# Fastino-connectors.net
KiCad netlist of a schematic drawn in Altium Designer
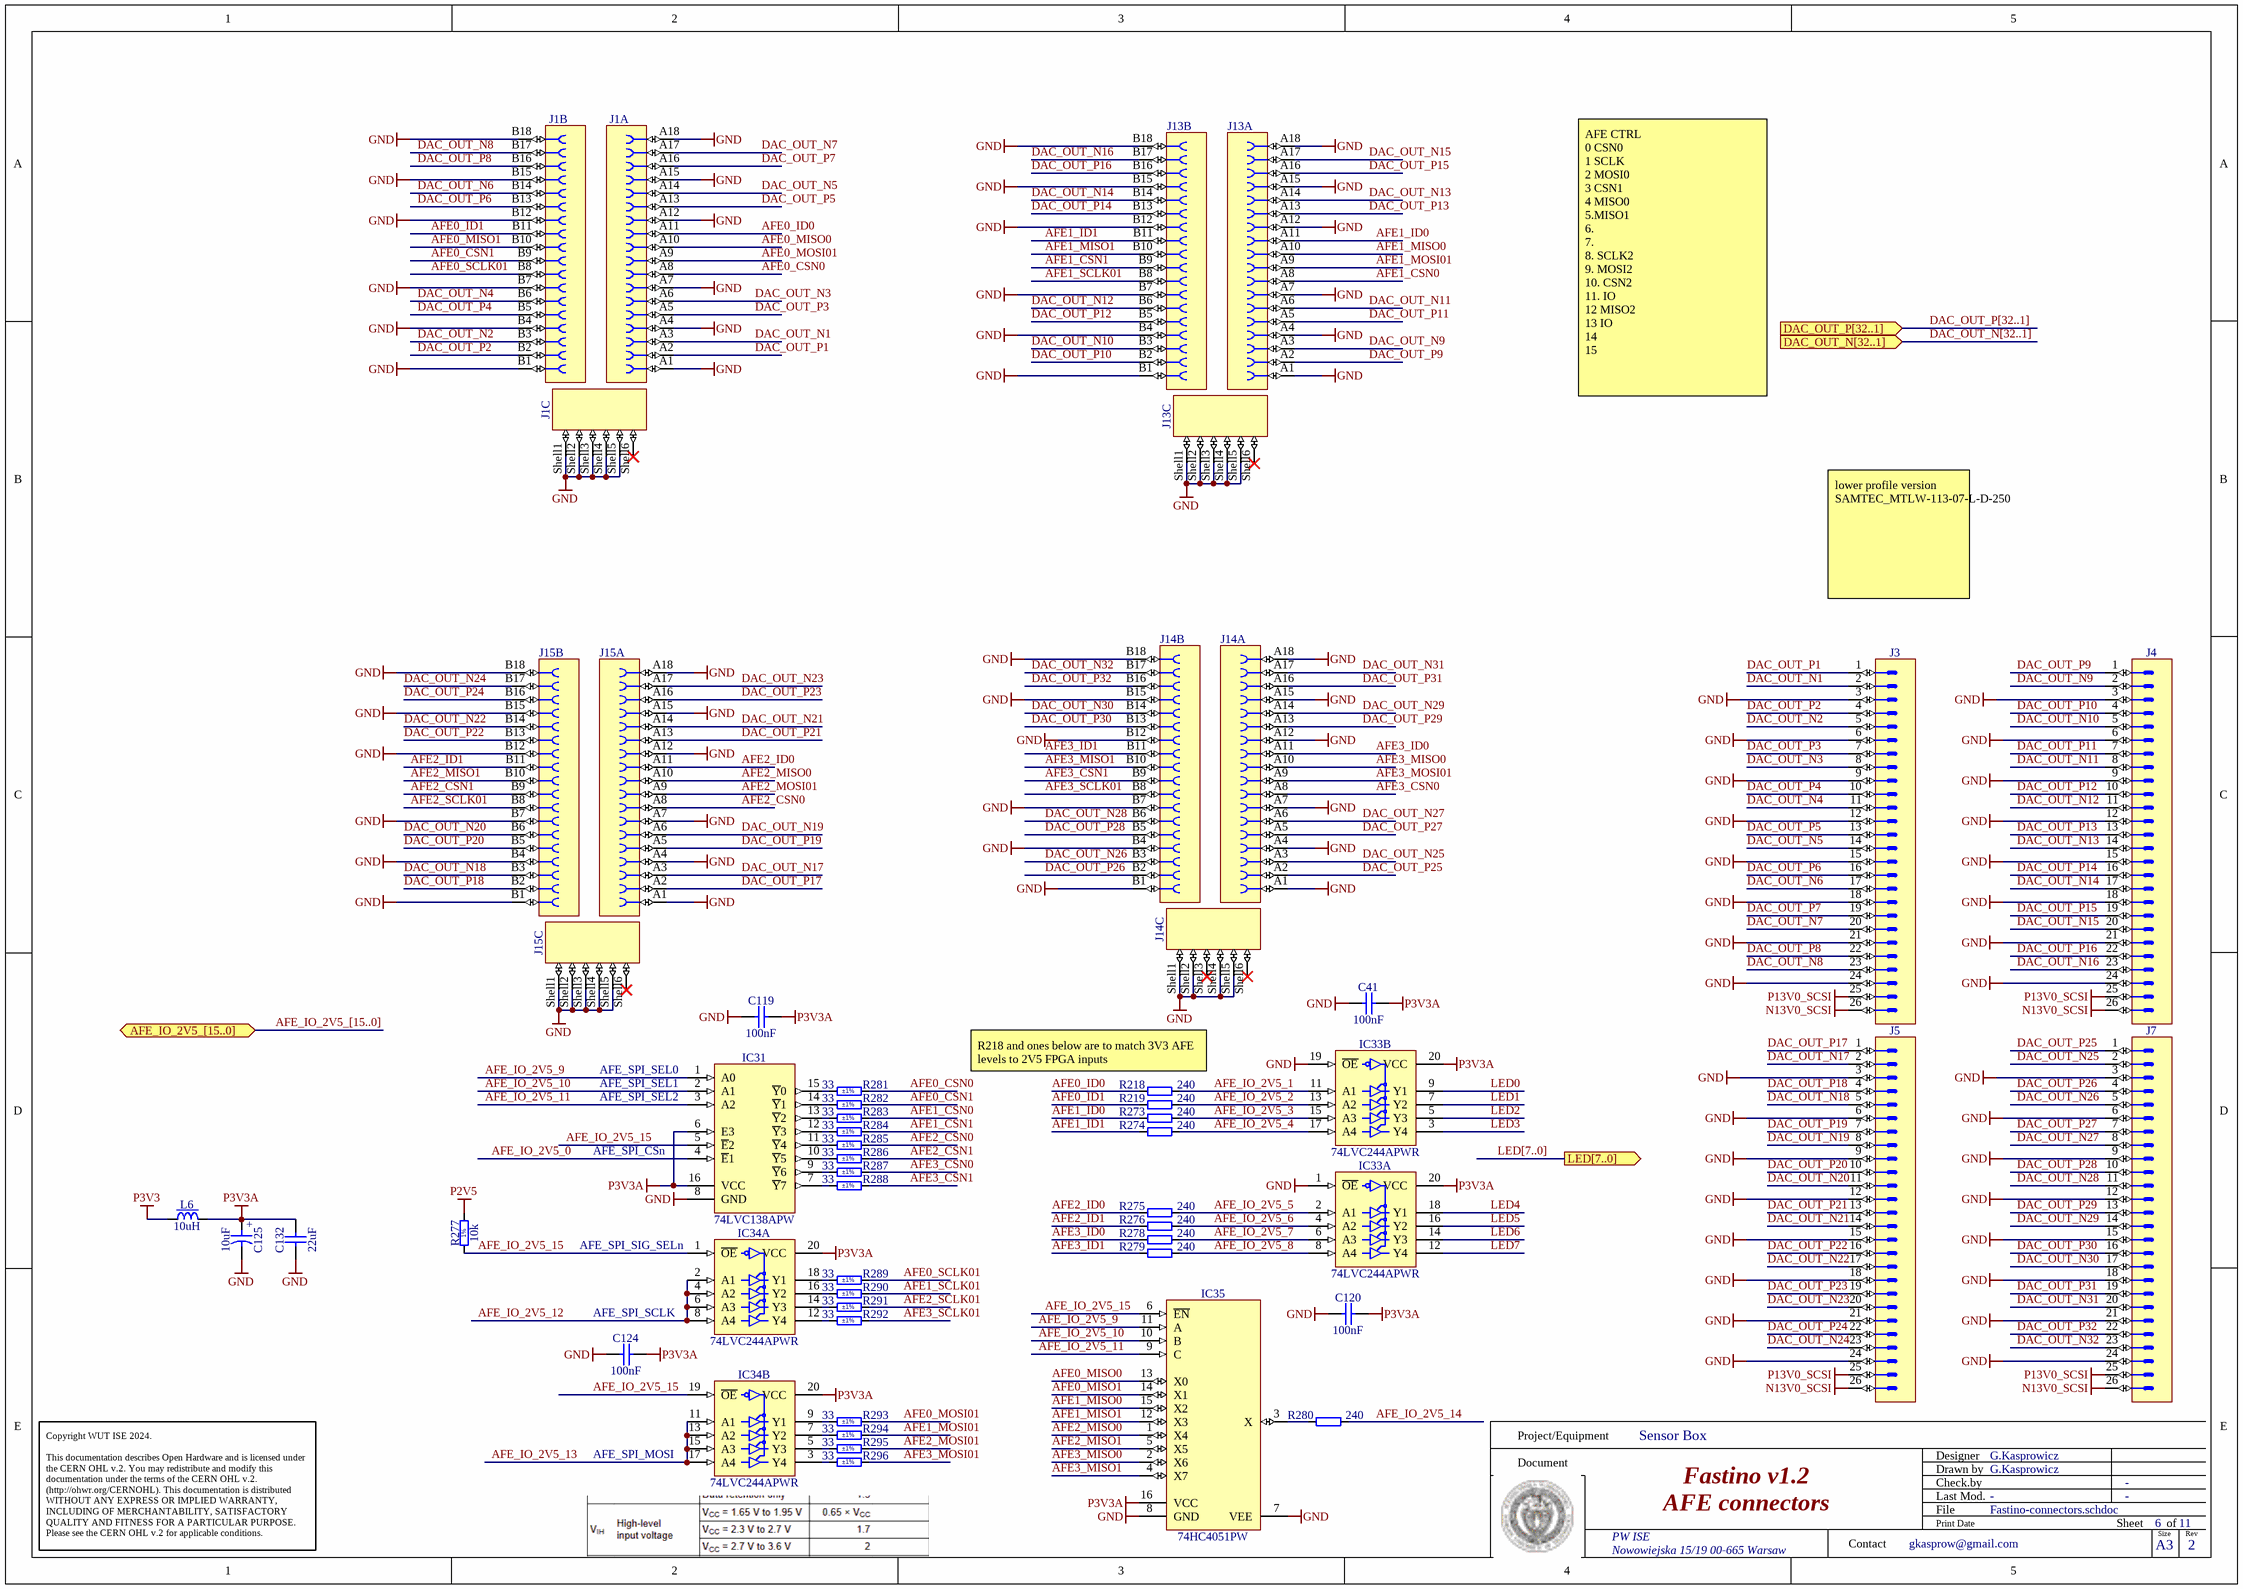
[diagram p0: Fastino-connectors.schdoc]

(export (version "E")
  (design (tool "Eeschema 10.0.6"))
  (components
    (comp (ref "C41")
      (value "100nF")
      (footprint "CAPC1005X55N")
      (description "Non-polarised capacitor")
      (fields
        (field (name "PART NUMBER") "CC0402_100NF_16V_10%_X5R")
        (field (name "VOLTAGE") "16V")
        (field (name "AUTHOR") "CERN DEM JLC")
      )
      (libsource (lib "Capacitors") (part "Capacitor - non polarized"))
    )
    (comp (ref "C119")
      (value "100nF")
      (footprint "CAPC1005X55N")
      (description "Non-polarised capacitor")
      (fields
        (field (name "PART NUMBER") "CC0402_100NF_16V_10%_X5R")
        (field (name "VOLTAGE") "16V")
        (field (name "AUTHOR") "CERN DEM JLC")
      )
      (libsource (lib "Capacitors") (part "Capacitor - non polarized"))
    )
    (comp (ref "C120")
      (value "100nF")
      (footprint "CAPC1005X55N")
      (description "Non-polarised capacitor")
      (fields
        (field (name "PART NUMBER") "CC0402_100NF_16V_10%_X5R")
        (field (name "VOLTAGE") "16V")
        (field (name "AUTHOR") "CERN DEM JLC")
      )
      (libsource (lib "Capacitors") (part "Capacitor - non polarized"))
    )
    (comp (ref "C124")
      (value "100nF")
      (footprint "CAPC1005X55N")
      (description "Non-polarised capacitor")
      (fields
        (field (name "PART NUMBER") "CC0402_100NF_16V_10%_X5R")
        (field (name "VOLTAGE") "16V")
        (field (name "AUTHOR") "CERN DEM JLC")
      )
      (libsource (lib "Capacitors") (part "Capacitor - non polarized"))
    )
    (comp (ref "C125")
      (value "10uF")
      (footprint "CAPMP3216X180N")
      (description "Polarised capacitor")
      (fields
        (field (name "PART NUMBER") "CTE3216-18_10UF_16V_20%_AVX_TCJ")
        (field (name "VOLTAGE") "16V")
        (field (name "AUTHOR") "CERN DEM JLC")
      )
      (libsource (lib "Capacitors") (part "Capacitor - polarized"))
    )
    (comp (ref "C132")
      (value "22uF")
      (footprint "CAPC2012X135N")
      (description "Non-polarised capacitor")
      (fields
        (field (name "PART NUMBER") "CC0805_22UF_16V_10%_X5R")
        (field (name "VOLTAGE") "16V")
        (field (name "AUTHOR") "CERN DEM JLC")
      )
      (libsource (lib "Capacitors") (part "Capacitor - non polarized"))
    )
    (comp (ref "IC31")
      (value "74LVC138APW")
      (footprint "SOP65P640X110-16N")
      (description "3-Line to 8-Line Decoder/Demultiplexer")
      (fields (field (name "MANUFACTURER") "NEXPERIA") (field (name "AUTHOR") "CERN DEM HF"))
      (libsource (lib "ICs And Semiconductors") (part "74138_a"))
    )
    (comp (ref "IC33")
      (value "74LVC244APWR")
      (footprint "SOP65P640X110-20N")
      (description "Octal Buffer/Driver with 3-State Ouputs")
      (fields
        (field (name "MANUFACTURER") "TEXAS INSTRUMENTS")
        (field (name "MANUFACTURER PART NUMBER") "74LVC244APW")
        (field (name "AUTHOR") "GK")
      )
      (libsource (lib "ICS-logic") (part "74LVC244APW"))
    )
    (comp (ref "IC34")
      (value "74LVC244APWR")
      (footprint "SOP65P640X110-20N")
      (description "Octal Buffer/Driver with 3-State Ouputs")
      (fields
        (field (name "MANUFACTURER") "TEXAS INSTRUMENTS")
        (field (name "MANUFACTURER PART NUMBER") "74LVC244APW")
        (field (name "AUTHOR") "GK")
      )
      (libsource (lib "ICS-logic") (part "74LVC244APW"))
    )
    (comp (ref "IC35")
      (value "74HC4051PW")
      (footprint "SOP65P640X120-16N")
      (description "8-Channel Analog Multiplexer/Demultiplexer")
      (fields (field (name "MANUFACTURER") "NXP") (field (name "AUTHOR") "GK"))
      (libsource (lib "ICS-logic") (part "74HC4051PW"))
    )
    (comp (ref "J1")
      (value "iPass™")
      (footprint "MOLEX_75783-0107")
      (fields
        (field (name "PART NUMBER") "MOLEX 75783-0107 / 75783-0136")
        (field (name "MANUFACTURER") "MOLEX")
        (field (name "MANUFACTURER PART NUMBER") "75783-0107 / 75783-0136")
        (field (name "AUTHOR") "CERN DEM JLC")
      )
      (libsource (lib "") (part "MOLEX_75783-0107_1"))
    )
    (comp (ref "J3")
      (value "Header 26")
      (footprint "3M_N2526-6002RB")
      (description "Connector 26 Male")
      (fields
        (field (name "PART NUMBER") "3M_N2526-6002RB")
        (field (name "MANUFACTURER") "3M")
        (field (name "AUTHOR") "CERN DEM JLC")
      )
      (libsource (lib "Connectors") (part "Connector 26 Male"))
    )
    (comp (ref "J4")
      (value "Header 26")
      (footprint "3M_N2526-6002RB")
      (description "Connector 26 Male")
      (fields
        (field (name "PART NUMBER") "3M_N2526-6002RB")
        (field (name "MANUFACTURER") "3M")
        (field (name "AUTHOR") "CERN DEM JLC")
      )
      (libsource (lib "Connectors") (part "Connector 26 Male"))
    )
    (comp (ref "J5")
      (value "Header 26")
      (footprint "3M_N2526-6002RB")
      (description "Connector 26 Male")
      (fields
        (field (name "PART NUMBER") "3M_N2526-6002RB")
        (field (name "MANUFACTURER") "3M")
        (field (name "AUTHOR") "CERN DEM JLC")
      )
      (libsource (lib "Connectors") (part "Connector 26 Male"))
    )
    (comp (ref "J7")
      (value "Header 26")
      (footprint "3M_N2526-6002RB")
      (description "Connector 26 Male")
      (fields
        (field (name "PART NUMBER") "3M_N2526-6002RB")
        (field (name "MANUFACTURER") "3M")
        (field (name "AUTHOR") "CERN DEM JLC")
      )
      (libsource (lib "Connectors") (part "Connector 26 Male"))
    )
    (comp (ref "J13")
      (value "iPass™")
      (footprint "MOLEX_75783-0107")
      (fields
        (field (name "PART NUMBER") "MOLEX 75783-0107 / 75783-0136")
        (field (name "MANUFACTURER") "MOLEX")
        (field (name "MANUFACTURER PART NUMBER") "75783-0107 / 75783-0136")
        (field (name "AUTHOR") "CERN DEM JLC")
      )
      (libsource (lib "Connectors") (part "MOLEX_75783-0107"))
    )
    (comp (ref "J14")
      (value "iPass™")
      (footprint "MOLEX_75783-0107")
      (fields
        (field (name "PART NUMBER") "MOLEX 75783-0107 / 75783-0136")
        (field (name "MANUFACTURER") "MOLEX")
        (field (name "MANUFACTURER PART NUMBER") "75783-0107 / 75783-0136")
        (field (name "AUTHOR") "CERN DEM JLC")
      )
      (libsource (lib "Connectors") (part "MOLEX_75783-0107"))
    )
    (comp (ref "J15")
      (value "iPass™")
      (footprint "MOLEX_75783-0107")
      (fields
        (field (name "PART NUMBER") "MOLEX 75783-0107 / 75783-0136")
        (field (name "MANUFACTURER") "MOLEX")
        (field (name "MANUFACTURER PART NUMBER") "75783-0107 / 75783-0136")
        (field (name "AUTHOR") "CERN DEM JLC")
      )
      (libsource (lib "") (part "MOLEX_75783-0107_2"))
    )
    (comp (ref "L6")
      (value "10uH")
      (footprint "IND_MURATA-PS_8400")
      (description "Inductor With Core")
      (fields
        (field (name "PART NUMBER") "IND_10UH_10%_MURATA-PS_8400")
        (field (name "POWER") "950mA")
        (field (name "AUTHOR") "CERN DEM JLC")
      )
      (libsource (lib "Inductors & Transformers") (part "Inductor With Magnetic core"))
    )
    (comp (ref "R218")
      (value "240")
      (footprint "RESC1005X40N")
      (description "Resistor - 1%")
      (fields
        (field (name "PART NUMBER") "R0402_240R_1%_0.0625W_100PPM")
        (field (name "POWER") "0.0625W")
        (field (name "AUTHOR") "CERN DEM JLC")
      )
      (libsource (lib "Resistors") (part "Resistor - 1%"))
    )
    (comp (ref "R219")
      (value "240")
      (footprint "RESC1005X40N")
      (description "Resistor - 1%")
      (fields
        (field (name "PART NUMBER") "R0402_240R_1%_0.0625W_100PPM")
        (field (name "POWER") "0.0625W")
        (field (name "AUTHOR") "CERN DEM JLC")
      )
      (libsource (lib "Resistors") (part "Resistor - 1%"))
    )
    (comp (ref "R273")
      (value "240")
      (footprint "RESC1005X40N")
      (description "Resistor - 1%")
      (fields
        (field (name "PART NUMBER") "R0402_240R_1%_0.0625W_100PPM")
        (field (name "POWER") "0.0625W")
        (field (name "AUTHOR") "CERN DEM JLC")
      )
      (libsource (lib "Resistors") (part "Resistor - 1%"))
    )
    (comp (ref "R274")
      (value "240")
      (footprint "RESC1005X40N")
      (description "Resistor - 1%")
      (fields
        (field (name "PART NUMBER") "R0402_240R_1%_0.0625W_100PPM")
        (field (name "POWER") "0.0625W")
        (field (name "AUTHOR") "CERN DEM JLC")
      )
      (libsource (lib "Resistors") (part "Resistor - 1%"))
    )
    (comp (ref "R275")
      (value "240")
      (footprint "RESC1005X40N")
      (description "Resistor - 1%")
      (fields
        (field (name "PART NUMBER") "R0402_240R_1%_0.0625W_100PPM")
        (field (name "POWER") "0.0625W")
        (field (name "AUTHOR") "CERN DEM JLC")
      )
      (libsource (lib "Resistors") (part "Resistor - 1%"))
    )
    (comp (ref "R276")
      (value "240")
      (footprint "RESC1005X40N")
      (description "Resistor - 1%")
      (fields
        (field (name "PART NUMBER") "R0402_240R_1%_0.0625W_100PPM")
        (field (name "POWER") "0.0625W")
        (field (name "AUTHOR") "CERN DEM JLC")
      )
      (libsource (lib "Resistors") (part "Resistor - 1%"))
    )
    (comp (ref "R277")
      (value "10k")
      (footprint "RESC1005X40N")
      (description "Resistor - 1%")
      (fields
        (field (name "PART NUMBER") "R0402_10K_1%_0.0625W_100PPM")
        (field (name "POWER") "0.0625W")
        (field (name "AUTHOR") "CERN DEM JLC")
      )
      (libsource (lib "Resistors") (part "Resistor - 1%"))
    )
    (comp (ref "R278")
      (value "240")
      (footprint "RESC1005X40N")
      (description "Resistor - 1%")
      (fields
        (field (name "PART NUMBER") "R0402_240R_1%_0.0625W_100PPM")
        (field (name "POWER") "0.0625W")
        (field (name "AUTHOR") "CERN DEM JLC")
      )
      (libsource (lib "Resistors") (part "Resistor - 1%"))
    )
    (comp (ref "R279")
      (value "240")
      (footprint "RESC1005X40N")
      (description "Resistor - 1%")
      (fields
        (field (name "PART NUMBER") "R0402_240R_1%_0.0625W_100PPM")
        (field (name "POWER") "0.0625W")
        (field (name "AUTHOR") "CERN DEM JLC")
      )
      (libsource (lib "Resistors") (part "Resistor - 1%"))
    )
    (comp (ref "R280")
      (value "240")
      (footprint "RESC1005X40N")
      (description "Resistor - 1%")
      (fields
        (field (name "PART NUMBER") "R0402_240R_1%_0.0625W_100PPM")
        (field (name "POWER") "0.0625W")
        (field (name "AUTHOR") "CERN DEM JLC")
      )
      (libsource (lib "Resistors") (part "Resistor - 1%"))
    )
    (comp (ref "R281")
      (value "33")
      (footprint "RESC1005X40N")
      (description "Resistor - 1%")
      (fields
        (field (name "TOLERANCE") "±1%")
        (field (name "PART NUMBER") "R0402_33R_1%_0.0625W_100PPM")
        (field (name "POWER") "0.0625W")
        (field (name "AUTHOR") "CERN DEM JLC")
      )
      (libsource (lib "Resistors") (part "Resistor - 1%"))
    )
    (comp (ref "R282")
      (value "33")
      (footprint "RESC1005X40N")
      (description "Resistor - 1%")
      (fields
        (field (name "TOLERANCE") "±1%")
        (field (name "PART NUMBER") "R0402_33R_1%_0.0625W_100PPM")
        (field (name "POWER") "0.0625W")
        (field (name "AUTHOR") "CERN DEM JLC")
      )
      (libsource (lib "Resistors") (part "Resistor - 1%"))
    )
    (comp (ref "R283")
      (value "33")
      (footprint "RESC1005X40N")
      (description "Resistor - 1%")
      (fields
        (field (name "TOLERANCE") "±1%")
        (field (name "PART NUMBER") "R0402_33R_1%_0.0625W_100PPM")
        (field (name "POWER") "0.0625W")
        (field (name "AUTHOR") "CERN DEM JLC")
      )
      (libsource (lib "Resistors") (part "Resistor - 1%"))
    )
    (comp (ref "R284")
      (value "33")
      (footprint "RESC1005X40N")
      (description "Resistor - 1%")
      (fields
        (field (name "TOLERANCE") "±1%")
        (field (name "PART NUMBER") "R0402_33R_1%_0.0625W_100PPM")
        (field (name "POWER") "0.0625W")
        (field (name "AUTHOR") "CERN DEM JLC")
      )
      (libsource (lib "Resistors") (part "Resistor - 1%"))
    )
    (comp (ref "R285")
      (value "33")
      (footprint "RESC1005X40N")
      (description "Resistor - 1%")
      (fields
        (field (name "TOLERANCE") "±1%")
        (field (name "PART NUMBER") "R0402_33R_1%_0.0625W_100PPM")
        (field (name "POWER") "0.0625W")
        (field (name "AUTHOR") "CERN DEM JLC")
      )
      (libsource (lib "Resistors") (part "Resistor - 1%"))
    )
    (comp (ref "R286")
      (value "33")
      (footprint "RESC1005X40N")
      (description "Resistor - 1%")
      (fields
        (field (name "TOLERANCE") "±1%")
        (field (name "PART NUMBER") "R0402_33R_1%_0.0625W_100PPM")
        (field (name "POWER") "0.0625W")
        (field (name "AUTHOR") "CERN DEM JLC")
      )
      (libsource (lib "Resistors") (part "Resistor - 1%"))
    )
    (comp (ref "R287")
      (value "33")
      (footprint "RESC1005X40N")
      (description "Resistor - 1%")
      (fields
        (field (name "TOLERANCE") "±1%")
        (field (name "PART NUMBER") "R0402_33R_1%_0.0625W_100PPM")
        (field (name "POWER") "0.0625W")
        (field (name "AUTHOR") "CERN DEM JLC")
      )
      (libsource (lib "Resistors") (part "Resistor - 1%"))
    )
    (comp (ref "R288")
      (value "33")
      (footprint "RESC1005X40N")
      (description "Resistor - 1%")
      (fields
        (field (name "TOLERANCE") "±1%")
        (field (name "PART NUMBER") "R0402_33R_1%_0.0625W_100PPM")
        (field (name "POWER") "0.0625W")
        (field (name "AUTHOR") "CERN DEM JLC")
      )
      (libsource (lib "Resistors") (part "Resistor - 1%"))
    )
    (comp (ref "R289")
      (value "33")
      (footprint "RESC1005X40N")
      (description "Resistor - 1%")
      (fields
        (field (name "TOLERANCE") "±1%")
        (field (name "PART NUMBER") "R0402_33R_1%_0.0625W_100PPM")
        (field (name "POWER") "0.0625W")
        (field (name "AUTHOR") "CERN DEM JLC")
      )
      (libsource (lib "Resistors") (part "Resistor - 1%"))
    )
    (comp (ref "R290")
      (value "33")
      (footprint "RESC1005X40N")
      (description "Resistor - 1%")
      (fields
        (field (name "TOLERANCE") "±1%")
        (field (name "PART NUMBER") "R0402_33R_1%_0.0625W_100PPM")
        (field (name "POWER") "0.0625W")
        (field (name "AUTHOR") "CERN DEM JLC")
      )
      (libsource (lib "Resistors") (part "Resistor - 1%"))
    )
    (comp (ref "R291")
      (value "33")
      (footprint "RESC1005X40N")
      (description "Resistor - 1%")
      (fields
        (field (name "TOLERANCE") "±1%")
        (field (name "PART NUMBER") "R0402_33R_1%_0.0625W_100PPM")
        (field (name "POWER") "0.0625W")
        (field (name "AUTHOR") "CERN DEM JLC")
      )
      (libsource (lib "Resistors") (part "Resistor - 1%"))
    )
    (comp (ref "R292")
      (value "33")
      (footprint "RESC1005X40N")
      (description "Resistor - 1%")
      (fields
        (field (name "TOLERANCE") "±1%")
        (field (name "PART NUMBER") "R0402_33R_1%_0.0625W_100PPM")
        (field (name "POWER") "0.0625W")
        (field (name "AUTHOR") "CERN DEM JLC")
      )
      (libsource (lib "Resistors") (part "Resistor - 1%"))
    )
    (comp (ref "R293")
      (value "33")
      (footprint "RESC1005X40N")
      (description "Resistor - 1%")
      (fields
        (field (name "TOLERANCE") "±1%")
        (field (name "PART NUMBER") "R0402_33R_1%_0.0625W_100PPM")
        (field (name "POWER") "0.0625W")
        (field (name "AUTHOR") "CERN DEM JLC")
      )
      (libsource (lib "Resistors") (part "Resistor - 1%"))
    )
    (comp (ref "R294")
      (value "33")
      (footprint "RESC1005X40N")
      (description "Resistor - 1%")
      (fields
        (field (name "TOLERANCE") "±1%")
        (field (name "PART NUMBER") "R0402_33R_1%_0.0625W_100PPM")
        (field (name "POWER") "0.0625W")
        (field (name "AUTHOR") "CERN DEM JLC")
      )
      (libsource (lib "Resistors") (part "Resistor - 1%"))
    )
    (comp (ref "R295")
      (value "33")
      (footprint "RESC1005X40N")
      (description "Resistor - 1%")
      (fields
        (field (name "TOLERANCE") "±1%")
        (field (name "PART NUMBER") "R0402_33R_1%_0.0625W_100PPM")
        (field (name "POWER") "0.0625W")
        (field (name "AUTHOR") "CERN DEM JLC")
      )
      (libsource (lib "Resistors") (part "Resistor - 1%"))
    )
    (comp (ref "R296")
      (value "33")
      (footprint "RESC1005X40N")
      (description "Resistor - 1%")
      (fields
        (field (name "TOLERANCE") "±1%")
        (field (name "PART NUMBER") "R0402_33R_1%_0.0625W_100PPM")
        (field (name "POWER") "0.0625W")
        (field (name "AUTHOR") "CERN DEM JLC")
      )
      (libsource (lib "Resistors") (part "Resistor - 1%"))
    )
  )
  (nets
    (net (code "1") (name "/AFE0_CSN0") (class "Default")
      (node (ref "J1") (pin "A8") (pinfunction "A8_A8") (pintype "bidirectional"))
      (node (ref "R281") (pin "2") (pinfunction "2_2") (pintype "passive"))
    )
    (net (code "2") (name "/AFE0_CSN1") (class "Default")
      (node (ref "J1") (pin "B9") (pinfunction "B9_B9") (pintype "bidirectional"))
      (node (ref "R282") (pin "2") (pinfunction "2_2") (pintype "passive"))
    )
    (net (code "3") (name "/AFE0_ID0") (class "Default")
      (node (ref "J1") (pin "A11") (pinfunction "A11_A11") (pintype "bidirectional"))
      (node (ref "R218") (pin "1") (pinfunction "1_1") (pintype "passive"))
    )
    (net (code "4") (name "/AFE0_ID1") (class "Default")
      (node (ref "J1") (pin "B11") (pinfunction "B11_B11") (pintype "bidirectional"))
      (node (ref "R219") (pin "1") (pinfunction "1_1") (pintype "passive"))
    )
    (net (code "5") (name "/AFE0_MISO0") (class "Default")
      (node (ref "IC35") (pin "13") (pinfunction "X0_13") (pintype "bidirectional"))
      (node (ref "J1") (pin "A10") (pinfunction "A10_A10") (pintype "bidirectional"))
    )
    (net (code "6") (name "/AFE0_MISO1") (class "Default")
      (node (ref "IC35") (pin "14") (pinfunction "X1_14") (pintype "bidirectional"))
      (node (ref "J1") (pin "B10") (pinfunction "B10_B10") (pintype "bidirectional"))
    )
    (net (code "7") (name "/AFE0_MOSI01") (class "Default")
      (node (ref "J1") (pin "A9") (pinfunction "A9_A9") (pintype "bidirectional"))
      (node (ref "R293") (pin "2") (pinfunction "2_2") (pintype "passive"))
    )
    (net (code "8") (name "/AFE0_SCLK01") (class "Default")
      (node (ref "J1") (pin "B8") (pinfunction "B8_B8") (pintype "bidirectional"))
      (node (ref "R289") (pin "2") (pinfunction "2_2") (pintype "passive"))
    )
    (net (code "9") (name "/AFE1_CSN0") (class "Default")
      (node (ref "J13") (pin "A8") (pinfunction "A8_A8") (pintype "bidirectional"))
      (node (ref "R283") (pin "2") (pinfunction "2_2") (pintype "passive"))
    )
    (net (code "10") (name "/AFE1_CSN1") (class "Default")
      (node (ref "J13") (pin "B9") (pinfunction "B9_B9") (pintype "bidirectional"))
      (node (ref "R284") (pin "2") (pinfunction "2_2") (pintype "passive"))
    )
    (net (code "11") (name "/AFE1_ID0") (class "Default")
      (node (ref "J13") (pin "A11") (pinfunction "A11_A11") (pintype "bidirectional"))
      (node (ref "R273") (pin "1") (pinfunction "1_1") (pintype "passive"))
    )
    (net (code "12") (name "/AFE1_ID1") (class "Default")
      (node (ref "J13") (pin "B11") (pinfunction "B11_B11") (pintype "bidirectional"))
      (node (ref "R274") (pin "1") (pinfunction "1_1") (pintype "passive"))
    )
    (net (code "13") (name "/AFE1_MISO0") (class "Default")
      (node (ref "IC35") (pin "15") (pinfunction "X2_15") (pintype "bidirectional"))
      (node (ref "J13") (pin "A10") (pinfunction "A10_A10") (pintype "bidirectional"))
    )
    (net (code "14") (name "/AFE1_MISO1") (class "Default")
      (node (ref "IC35") (pin "12") (pinfunction "X3_12") (pintype "bidirectional"))
      (node (ref "J13") (pin "B10") (pinfunction "B10_B10") (pintype "bidirectional"))
    )
    (net (code "15") (name "/AFE1_MOSI01") (class "Default")
      (node (ref "J13") (pin "A9") (pinfunction "A9_A9") (pintype "bidirectional"))
      (node (ref "R294") (pin "2") (pinfunction "2_2") (pintype "passive"))
    )
    (net (code "16") (name "/AFE1_SCLK01") (class "Default")
      (node (ref "J13") (pin "B8") (pinfunction "B8_B8") (pintype "bidirectional"))
      (node (ref "R290") (pin "2") (pinfunction "2_2") (pintype "passive"))
    )
    (net (code "17") (name "/AFE2_CSN0") (class "Default")
      (node (ref "J15") (pin "A8") (pinfunction "A8_A8") (pintype "bidirectional"))
      (node (ref "R285") (pin "2") (pinfunction "2_2") (pintype "passive"))
    )
    (net (code "18") (name "/AFE2_CSN1") (class "Default")
      (node (ref "J15") (pin "B9") (pinfunction "B9_B9") (pintype "bidirectional"))
      (node (ref "R286") (pin "2") (pinfunction "2_2") (pintype "passive"))
    )
    (net (code "19") (name "/AFE2_ID0") (class "Default")
      (node (ref "J15") (pin "A11") (pinfunction "A11_A11") (pintype "bidirectional"))
      (node (ref "R275") (pin "1") (pinfunction "1_1") (pintype "passive"))
    )
    (net (code "20") (name "/AFE2_ID1") (class "Default")
      (node (ref "J15") (pin "B11") (pinfunction "B11_B11") (pintype "bidirectional"))
      (node (ref "R276") (pin "1") (pinfunction "1_1") (pintype "passive"))
    )
    (net (code "21") (name "/AFE2_MISO0") (class "Default")
      (node (ref "IC35") (pin "1") (pinfunction "X4_1") (pintype "bidirectional"))
      (node (ref "J15") (pin "A10") (pinfunction "A10_A10") (pintype "bidirectional"))
    )
    (net (code "22") (name "/AFE2_MISO1") (class "Default")
      (node (ref "IC35") (pin "5") (pinfunction "X5_5") (pintype "bidirectional"))
      (node (ref "J15") (pin "B10") (pinfunction "B10_B10") (pintype "bidirectional"))
    )
    (net (code "23") (name "/AFE2_MOSI01") (class "Default")
      (node (ref "J15") (pin "A9") (pinfunction "A9_A9") (pintype "bidirectional"))
      (node (ref "R295") (pin "2") (pinfunction "2_2") (pintype "passive"))
    )
    (net (code "24") (name "/AFE2_SCLK01") (class "Default")
      (node (ref "J15") (pin "B8") (pinfunction "B8_B8") (pintype "bidirectional"))
      (node (ref "R291") (pin "2") (pinfunction "2_2") (pintype "passive"))
    )
    (net (code "25") (name "/AFE3_CSN0") (class "Default")
      (node (ref "J14") (pin "A8") (pinfunction "A8_A8") (pintype "bidirectional"))
      (node (ref "R287") (pin "2") (pinfunction "2_2") (pintype "passive"))
    )
    (net (code "26") (name "/AFE3_CSN1") (class "Default")
      (node (ref "J14") (pin "B9") (pinfunction "B9_B9") (pintype "bidirectional"))
      (node (ref "R288") (pin "2") (pinfunction "2_2") (pintype "passive"))
    )
    (net (code "27") (name "/AFE3_ID0") (class "Default")
      (node (ref "J14") (pin "A11") (pinfunction "A11_A11") (pintype "bidirectional"))
      (node (ref "R278") (pin "1") (pinfunction "1_1") (pintype "passive"))
    )
    (net (code "28") (name "/AFE3_ID1") (class "Default")
      (node (ref "J14") (pin "B11") (pinfunction "B11_B11") (pintype "bidirectional"))
      (node (ref "R279") (pin "1") (pinfunction "1_1") (pintype "passive"))
    )
    (net (code "29") (name "/AFE3_MISO0") (class "Default")
      (node (ref "IC35") (pin "2") (pinfunction "X6_2") (pintype "bidirectional"))
      (node (ref "J14") (pin "A10") (pinfunction "A10_A10") (pintype "bidirectional"))
    )
    (net (code "30") (name "/AFE3_MISO1") (class "Default")
      (node (ref "IC35") (pin "4") (pinfunction "X7_4") (pintype "bidirectional"))
      (node (ref "J14") (pin "B10") (pinfunction "B10_B10") (pintype "bidirectional"))
    )
    (net (code "31") (name "/AFE3_MOSI01") (class "Default")
      (node (ref "J14") (pin "A9") (pinfunction "A9_A9") (pintype "bidirectional"))
      (node (ref "R296") (pin "2") (pinfunction "2_2") (pintype "passive"))
    )
    (net (code "32") (name "/AFE3_SCLK01") (class "Default")
      (node (ref "J14") (pin "B8") (pinfunction "B8_B8") (pintype "bidirectional"))
      (node (ref "R292") (pin "2") (pinfunction "2_2") (pintype "passive"))
    )
    (net (code "33") (name "/AFE_IO_2V5_0") (class "Default")
      (node (ref "IC31") (pin "4") (pinfunction "~{E}1_4") (pintype "input"))
    )
    (net (code "34") (name "/AFE_IO_2V5_1") (class "Default")
      (node (ref "IC33") (pin "11") (pinfunction "A1_11") (pintype "input"))
      (node (ref "R218") (pin "2") (pinfunction "2_2") (pintype "passive"))
    )
    (net (code "35") (name "/AFE_IO_2V5_2") (class "Default")
      (node (ref "IC33") (pin "13") (pinfunction "A2_13") (pintype "input"))
      (node (ref "R219") (pin "2") (pinfunction "2_2") (pintype "passive"))
    )
    (net (code "36") (name "/AFE_IO_2V5_3") (class "Default")
      (node (ref "IC33") (pin "15") (pinfunction "A3_15") (pintype "input"))
      (node (ref "R273") (pin "2") (pinfunction "2_2") (pintype "passive"))
    )
    (net (code "37") (name "/AFE_IO_2V5_4") (class "Default")
      (node (ref "IC33") (pin "17") (pinfunction "A4_17") (pintype "input"))
      (node (ref "R274") (pin "2") (pinfunction "2_2") (pintype "passive"))
    )
    (net (code "38") (name "/AFE_IO_2V5_5") (class "Default")
      (node (ref "IC33") (pin "2") (pinfunction "A1_2") (pintype "input"))
      (node (ref "R275") (pin "2") (pinfunction "2_2") (pintype "passive"))
    )
    (net (code "39") (name "/AFE_IO_2V5_6") (class "Default")
      (node (ref "IC33") (pin "4") (pinfunction "A2_4") (pintype "input"))
      (node (ref "R276") (pin "2") (pinfunction "2_2") (pintype "passive"))
    )
    (net (code "40") (name "/AFE_IO_2V5_7") (class "Default")
      (node (ref "IC33") (pin "6") (pinfunction "A3_6") (pintype "input"))
      (node (ref "R278") (pin "2") (pinfunction "2_2") (pintype "passive"))
    )
    (net (code "41") (name "/AFE_IO_2V5_8") (class "Default")
      (node (ref "IC33") (pin "8") (pinfunction "A4_8") (pintype "input"))
      (node (ref "R279") (pin "2") (pinfunction "2_2") (pintype "passive"))
    )
    (net (code "42") (name "/AFE_IO_2V5_9") (class "Default")
      (node (ref "IC31") (pin "1") (pinfunction "A0_1") (pintype "input"))
      (node (ref "IC35") (pin "11") (pinfunction "A_11") (pintype "input"))
    )
    (net (code "43") (name "/AFE_IO_2V5_10") (class "Default")
      (node (ref "IC31") (pin "2") (pinfunction "A1_2") (pintype "input"))
      (node (ref "IC35") (pin "10") (pinfunction "B_10") (pintype "input"))
    )
    (net (code "44") (name "/AFE_IO_2V5_11") (class "Default")
      (node (ref "IC31") (pin "3") (pinfunction "A2_3") (pintype "input"))
      (node (ref "IC35") (pin "9") (pinfunction "C_9") (pintype "input"))
    )
    (net (code "45") (name "/AFE_IO_2V5_12") (class "Default")
      (node (ref "IC34") (pin "2") (pinfunction "A1_2") (pintype "input"))
      (node (ref "IC34") (pin "4") (pinfunction "A2_4") (pintype "input"))
      (node (ref "IC34") (pin "6") (pinfunction "A3_6") (pintype "input"))
      (node (ref "IC34") (pin "8") (pinfunction "A4_8") (pintype "input"))
    )
    (net (code "46") (name "/AFE_IO_2V5_13") (class "Default")
      (node (ref "IC34") (pin "11") (pinfunction "A1_11") (pintype "input"))
      (node (ref "IC34") (pin "13") (pinfunction "A2_13") (pintype "input"))
      (node (ref "IC34") (pin "15") (pinfunction "A3_15") (pintype "input"))
      (node (ref "IC34") (pin "17") (pinfunction "A4_17") (pintype "input"))
    )
    (net (code "47") (name "/AFE_IO_2V5_14") (class "Default")
      (node (ref "R280") (pin "2") (pinfunction "2_2") (pintype "passive"))
    )
    (net (code "48") (name "/AFE_IO_2V5_15") (class "Default")
      (node (ref "IC31") (pin "5") (pinfunction "~{E}2_5") (pintype "input"))
      (node (ref "IC34") (pin "1") (pinfunction "~{OE}_1") (pintype "input"))
      (node (ref "IC34") (pin "19") (pinfunction "~{OE}_19") (pintype "input"))
      (node (ref "IC35") (pin "6") (pinfunction "~{EN}_6") (pintype "input"))
      (node (ref "R277") (pin "1") (pinfunction "1_1") (pintype "passive"))
    )
    (net (code "50") (name "/DAC_OUT_N1") (class "Default")
      (node (ref "J1") (pin "A3") (pinfunction "A3_A3") (pintype "bidirectional"))
      (node (ref "J3") (pin "2") (pinfunction "2_2") (pintype "bidirectional"))
    )
    (net (code "51") (name "/DAC_OUT_N2") (class "Default")
      (node (ref "J1") (pin "B3") (pinfunction "B3_B3") (pintype "bidirectional"))
      (node (ref "J3") (pin "5") (pinfunction "5_5") (pintype "bidirectional"))
    )
    (net (code "52") (name "/DAC_OUT_N3") (class "Default")
      (node (ref "J1") (pin "A6") (pinfunction "A6_A6") (pintype "bidirectional"))
      (node (ref "J3") (pin "8") (pinfunction "8_8") (pintype "bidirectional"))
    )
    (net (code "53") (name "/DAC_OUT_N4") (class "Default")
      (node (ref "J1") (pin "B6") (pinfunction "B6_B6") (pintype "bidirectional"))
      (node (ref "J3") (pin "11") (pinfunction "11_11") (pintype "bidirectional"))
    )
    (net (code "54") (name "/DAC_OUT_N5") (class "Default")
      (node (ref "J1") (pin "A14") (pinfunction "A14_A14") (pintype "bidirectional"))
      (node (ref "J3") (pin "14") (pinfunction "14_14") (pintype "bidirectional"))
    )
    (net (code "55") (name "/DAC_OUT_N6") (class "Default")
      (node (ref "J1") (pin "B14") (pinfunction "B14_B14") (pintype "bidirectional"))
      (node (ref "J3") (pin "17") (pinfunction "17_17") (pintype "bidirectional"))
    )
    (net (code "56") (name "/DAC_OUT_N7") (class "Default")
      (node (ref "J1") (pin "A17") (pinfunction "A17_A17") (pintype "bidirectional"))
      (node (ref "J3") (pin "20") (pinfunction "20_20") (pintype "bidirectional"))
    )
    (net (code "57") (name "/DAC_OUT_N8") (class "Default")
      (node (ref "J1") (pin "B17") (pinfunction "B17_B17") (pintype "bidirectional"))
      (node (ref "J3") (pin "23") (pinfunction "23_23") (pintype "bidirectional"))
    )
    (net (code "58") (name "/DAC_OUT_N9") (class "Default")
      (node (ref "J13") (pin "A3") (pinfunction "A3_A3") (pintype "bidirectional"))
      (node (ref "J4") (pin "2") (pinfunction "2_2") (pintype "bidirectional"))
    )
    (net (code "59") (name "/DAC_OUT_N10") (class "Default")
      (node (ref "J13") (pin "B3") (pinfunction "B3_B3") (pintype "bidirectional"))
      (node (ref "J4") (pin "5") (pinfunction "5_5") (pintype "bidirectional"))
    )
    (net (code "60") (name "/DAC_OUT_N11") (class "Default")
      (node (ref "J13") (pin "A6") (pinfunction "A6_A6") (pintype "bidirectional"))
      (node (ref "J4") (pin "8") (pinfunction "8_8") (pintype "bidirectional"))
    )
    (net (code "61") (name "/DAC_OUT_N12") (class "Default")
      (node (ref "J13") (pin "B6") (pinfunction "B6_B6") (pintype "bidirectional"))
      (node (ref "J4") (pin "11") (pinfunction "11_11") (pintype "bidirectional"))
    )
    (net (code "62") (name "/DAC_OUT_N13") (class "Default")
      (node (ref "J13") (pin "A14") (pinfunction "A14_A14") (pintype "bidirectional"))
      (node (ref "J4") (pin "14") (pinfunction "14_14") (pintype "bidirectional"))
    )
    (net (code "63") (name "/DAC_OUT_N14") (class "Default")
      (node (ref "J13") (pin "B14") (pinfunction "B14_B14") (pintype "bidirectional"))
      (node (ref "J4") (pin "17") (pinfunction "17_17") (pintype "bidirectional"))
    )
    (net (code "64") (name "/DAC_OUT_N15") (class "Default")
      (node (ref "J13") (pin "A17") (pinfunction "A17_A17") (pintype "bidirectional"))
      (node (ref "J4") (pin "20") (pinfunction "20_20") (pintype "bidirectional"))
    )
    (net (code "65") (name "/DAC_OUT_N16") (class "Default")
      (node (ref "J13") (pin "B17") (pinfunction "B17_B17") (pintype "bidirectional"))
      (node (ref "J4") (pin "23") (pinfunction "23_23") (pintype "bidirectional"))
    )
    (net (code "66") (name "/DAC_OUT_N17") (class "Default")
      (node (ref "J15") (pin "A3") (pinfunction "A3_A3") (pintype "bidirectional"))
      (node (ref "J5") (pin "2") (pinfunction "2_2") (pintype "bidirectional"))
    )
    (net (code "67") (name "/DAC_OUT_N18") (class "Default")
      (node (ref "J15") (pin "B3") (pinfunction "B3_B3") (pintype "bidirectional"))
      (node (ref "J5") (pin "5") (pinfunction "5_5") (pintype "bidirectional"))
    )
    (net (code "68") (name "/DAC_OUT_N19") (class "Default")
      (node (ref "J15") (pin "A6") (pinfunction "A6_A6") (pintype "bidirectional"))
      (node (ref "J5") (pin "8") (pinfunction "8_8") (pintype "bidirectional"))
    )
    (net (code "69") (name "/DAC_OUT_N20") (class "Default")
      (node (ref "J15") (pin "B6") (pinfunction "B6_B6") (pintype "bidirectional"))
      (node (ref "J5") (pin "11") (pinfunction "11_11") (pintype "bidirectional"))
    )
    (net (code "70") (name "/DAC_OUT_N21") (class "Default")
      (node (ref "J15") (pin "A14") (pinfunction "A14_A14") (pintype "bidirectional"))
      (node (ref "J5") (pin "14") (pinfunction "14_14") (pintype "bidirectional"))
    )
    (net (code "71") (name "/DAC_OUT_N22") (class "Default")
      (node (ref "J15") (pin "B14") (pinfunction "B14_B14") (pintype "bidirectional"))
      (node (ref "J5") (pin "17") (pinfunction "17_17") (pintype "bidirectional"))
    )
    (net (code "72") (name "/DAC_OUT_N23") (class "Default")
      (node (ref "J15") (pin "A17") (pinfunction "A17_A17") (pintype "bidirectional"))
      (node (ref "J5") (pin "20") (pinfunction "20_20") (pintype "bidirectional"))
    )
    (net (code "73") (name "/DAC_OUT_N24") (class "Default")
      (node (ref "J15") (pin "B17") (pinfunction "B17_B17") (pintype "bidirectional"))
      (node (ref "J5") (pin "23") (pinfunction "23_23") (pintype "bidirectional"))
    )
    (net (code "74") (name "/DAC_OUT_N25") (class "Default")
      (node (ref "J14") (pin "A3") (pinfunction "A3_A3") (pintype "bidirectional"))
      (node (ref "J7") (pin "2") (pinfunction "2_2") (pintype "bidirectional"))
    )
    (net (code "75") (name "/DAC_OUT_N26") (class "Default")
      (node (ref "J14") (pin "B3") (pinfunction "B3_B3") (pintype "bidirectional"))
      (node (ref "J7") (pin "5") (pinfunction "5_5") (pintype "bidirectional"))
    )
    (net (code "76") (name "/DAC_OUT_N27") (class "Default")
      (node (ref "J14") (pin "A6") (pinfunction "A6_A6") (pintype "bidirectional"))
      (node (ref "J7") (pin "8") (pinfunction "8_8") (pintype "bidirectional"))
    )
    (net (code "77") (name "/DAC_OUT_N28") (class "Default")
      (node (ref "J14") (pin "B6") (pinfunction "B6_B6") (pintype "bidirectional"))
      (node (ref "J7") (pin "11") (pinfunction "11_11") (pintype "bidirectional"))
    )
    (net (code "78") (name "/DAC_OUT_N29") (class "Default")
      (node (ref "J14") (pin "A14") (pinfunction "A14_A14") (pintype "bidirectional"))
      (node (ref "J7") (pin "14") (pinfunction "14_14") (pintype "bidirectional"))
    )
    (net (code "79") (name "/DAC_OUT_N30") (class "Default")
      (node (ref "J14") (pin "B14") (pinfunction "B14_B14") (pintype "bidirectional"))
      (node (ref "J7") (pin "17") (pinfunction "17_17") (pintype "bidirectional"))
    )
    (net (code "80") (name "/DAC_OUT_N31") (class "Default")
      (node (ref "J14") (pin "A17") (pinfunction "A17_A17") (pintype "bidirectional"))
      (node (ref "J7") (pin "20") (pinfunction "20_20") (pintype "bidirectional"))
    )
    (net (code "81") (name "/DAC_OUT_N32") (class "Default")
      (node (ref "J14") (pin "B17") (pinfunction "B17_B17") (pintype "bidirectional"))
      (node (ref "J7") (pin "23") (pinfunction "23_23") (pintype "bidirectional"))
    )
    (net (code "83") (name "/DAC_OUT_P1") (class "Default")
      (node (ref "J1") (pin "A2") (pinfunction "A2_A2") (pintype "bidirectional"))
      (node (ref "J3") (pin "1") (pinfunction "1_1") (pintype "bidirectional"))
    )
    (net (code "84") (name "/DAC_OUT_P2") (class "Default")
      (node (ref "J1") (pin "B2") (pinfunction "B2_B2") (pintype "bidirectional"))
      (node (ref "J3") (pin "4") (pinfunction "4_4") (pintype "bidirectional"))
    )
    (net (code "85") (name "/DAC_OUT_P3") (class "Default")
      (node (ref "J1") (pin "A5") (pinfunction "A5_A5") (pintype "bidirectional"))
      (node (ref "J3") (pin "7") (pinfunction "7_7") (pintype "bidirectional"))
    )
    (net (code "86") (name "/DAC_OUT_P4") (class "Default")
      (node (ref "J1") (pin "B5") (pinfunction "B5_B5") (pintype "bidirectional"))
      (node (ref "J3") (pin "10") (pinfunction "10_10") (pintype "bidirectional"))
    )
    (net (code "87") (name "/DAC_OUT_P5") (class "Default")
      (node (ref "J1") (pin "A13") (pinfunction "A13_A13") (pintype "bidirectional"))
      (node (ref "J3") (pin "13") (pinfunction "13_13") (pintype "bidirectional"))
    )
    (net (code "88") (name "/DAC_OUT_P6") (class "Default")
      (node (ref "J1") (pin "B13") (pinfunction "B13_B13") (pintype "bidirectional"))
      (node (ref "J3") (pin "16") (pinfunction "16_16") (pintype "bidirectional"))
    )
    (net (code "89") (name "/DAC_OUT_P7") (class "Default")
      (node (ref "J1") (pin "A16") (pinfunction "A16_A16") (pintype "bidirectional"))
      (node (ref "J3") (pin "19") (pinfunction "19_19") (pintype "bidirectional"))
    )
    (net (code "90") (name "/DAC_OUT_P8") (class "Default")
      (node (ref "J1") (pin "B16") (pinfunction "B16_B16") (pintype "bidirectional"))
      (node (ref "J3") (pin "22") (pinfunction "22_22") (pintype "bidirectional"))
    )
    (net (code "91") (name "/DAC_OUT_P9") (class "Default")
      (node (ref "J13") (pin "A2") (pinfunction "A2_A2") (pintype "bidirectional"))
      (node (ref "J4") (pin "1") (pinfunction "1_1") (pintype "bidirectional"))
    )
    (net (code "92") (name "/DAC_OUT_P10") (class "Default")
      (node (ref "J13") (pin "B2") (pinfunction "B2_B2") (pintype "bidirectional"))
      (node (ref "J4") (pin "4") (pinfunction "4_4") (pintype "bidirectional"))
    )
    (net (code "93") (name "/DAC_OUT_P11") (class "Default")
      (node (ref "J13") (pin "A5") (pinfunction "A5_A5") (pintype "bidirectional"))
      (node (ref "J4") (pin "7") (pinfunction "7_7") (pintype "bidirectional"))
    )
    (net (code "94") (name "/DAC_OUT_P12") (class "Default")
      (node (ref "J13") (pin "B5") (pinfunction "B5_B5") (pintype "bidirectional"))
      (node (ref "J4") (pin "10") (pinfunction "10_10") (pintype "bidirectional"))
    )
    (net (code "95") (name "/DAC_OUT_P13") (class "Default")
      (node (ref "J13") (pin "A13") (pinfunction "A13_A13") (pintype "bidirectional"))
      (node (ref "J4") (pin "13") (pinfunction "13_13") (pintype "bidirectional"))
    )
    (net (code "96") (name "/DAC_OUT_P14") (class "Default")
      (node (ref "J13") (pin "B13") (pinfunction "B13_B13") (pintype "bidirectional"))
      (node (ref "J4") (pin "16") (pinfunction "16_16") (pintype "bidirectional"))
    )
    (net (code "97") (name "/DAC_OUT_P15") (class "Default")
      (node (ref "J13") (pin "A16") (pinfunction "A16_A16") (pintype "bidirectional"))
      (node (ref "J4") (pin "19") (pinfunction "19_19") (pintype "bidirectional"))
    )
    (net (code "98") (name "/DAC_OUT_P16") (class "Default")
      (node (ref "J13") (pin "B16") (pinfunction "B16_B16") (pintype "bidirectional"))
      (node (ref "J4") (pin "22") (pinfunction "22_22") (pintype "bidirectional"))
    )
    (net (code "99") (name "/DAC_OUT_P17") (class "Default")
      (node (ref "J15") (pin "A2") (pinfunction "A2_A2") (pintype "bidirectional"))
      (node (ref "J5") (pin "1") (pinfunction "1_1") (pintype "bidirectional"))
    )
    (net (code "100") (name "/DAC_OUT_P18") (class "Default")
      (node (ref "J15") (pin "B2") (pinfunction "B2_B2") (pintype "bidirectional"))
      (node (ref "J5") (pin "4") (pinfunction "4_4") (pintype "bidirectional"))
    )
    (net (code "101") (name "/DAC_OUT_P19") (class "Default")
      (node (ref "J15") (pin "A5") (pinfunction "A5_A5") (pintype "bidirectional"))
      (node (ref "J5") (pin "7") (pinfunction "7_7") (pintype "bidirectional"))
    )
    (net (code "102") (name "/DAC_OUT_P20") (class "Default")
      (node (ref "J15") (pin "B5") (pinfunction "B5_B5") (pintype "bidirectional"))
      (node (ref "J5") (pin "10") (pinfunction "10_10") (pintype "bidirectional"))
    )
    (net (code "103") (name "/DAC_OUT_P21") (class "Default")
      (node (ref "J15") (pin "A13") (pinfunction "A13_A13") (pintype "bidirectional"))
      (node (ref "J5") (pin "13") (pinfunction "13_13") (pintype "bidirectional"))
    )
    (net (code "104") (name "/DAC_OUT_P22") (class "Default")
      (node (ref "J15") (pin "B13") (pinfunction "B13_B13") (pintype "bidirectional"))
      (node (ref "J5") (pin "16") (pinfunction "16_16") (pintype "bidirectional"))
    )
    (net (code "105") (name "/DAC_OUT_P23") (class "Default")
      (node (ref "J15") (pin "A16") (pinfunction "A16_A16") (pintype "bidirectional"))
      (node (ref "J5") (pin "19") (pinfunction "19_19") (pintype "bidirectional"))
    )
    (net (code "106") (name "/DAC_OUT_P24") (class "Default")
      (node (ref "J15") (pin "B16") (pinfunction "B16_B16") (pintype "bidirectional"))
      (node (ref "J5") (pin "22") (pinfunction "22_22") (pintype "bidirectional"))
    )
    (net (code "107") (name "/DAC_OUT_P25") (class "Default")
      (node (ref "J14") (pin "A2") (pinfunction "A2_A2") (pintype "bidirectional"))
      (node (ref "J7") (pin "1") (pinfunction "1_1") (pintype "bidirectional"))
    )
    (net (code "108") (name "/DAC_OUT_P26") (class "Default")
      (node (ref "J14") (pin "B2") (pinfunction "B2_B2") (pintype "bidirectional"))
      (node (ref "J7") (pin "4") (pinfunction "4_4") (pintype "bidirectional"))
    )
    (net (code "109") (name "/DAC_OUT_P27") (class "Default")
      (node (ref "J14") (pin "A5") (pinfunction "A5_A5") (pintype "bidirectional"))
      (node (ref "J7") (pin "7") (pinfunction "7_7") (pintype "bidirectional"))
    )
    (net (code "110") (name "/DAC_OUT_P28") (class "Default")
      (node (ref "J14") (pin "B5") (pinfunction "B5_B5") (pintype "bidirectional"))
      (node (ref "J7") (pin "10") (pinfunction "10_10") (pintype "bidirectional"))
    )
    (net (code "111") (name "/DAC_OUT_P29") (class "Default")
      (node (ref "J14") (pin "A13") (pinfunction "A13_A13") (pintype "bidirectional"))
      (node (ref "J7") (pin "13") (pinfunction "13_13") (pintype "bidirectional"))
    )
    (net (code "112") (name "/DAC_OUT_P30") (class "Default")
      (node (ref "J14") (pin "B13") (pinfunction "B13_B13") (pintype "bidirectional"))
      (node (ref "J7") (pin "16") (pinfunction "16_16") (pintype "bidirectional"))
    )
    (net (code "113") (name "/DAC_OUT_P31") (class "Default")
      (node (ref "J14") (pin "A16") (pinfunction "A16_A16") (pintype "bidirectional"))
      (node (ref "J7") (pin "19") (pinfunction "19_19") (pintype "bidirectional"))
    )
    (net (code "114") (name "/DAC_OUT_P32") (class "Default")
      (node (ref "J14") (pin "B16") (pinfunction "B16_B16") (pintype "bidirectional"))
      (node (ref "J7") (pin "22") (pinfunction "22_22") (pintype "bidirectional"))
    )
    (net (code "116") (name "/LED0") (class "Default")
      (node (ref "IC33") (pin "9") (pinfunction "Y1_9") (pintype "tri_state"))
    )
    (net (code "117") (name "/LED1") (class "Default")
      (node (ref "IC33") (pin "7") (pinfunction "Y2_7") (pintype "tri_state"))
    )
    (net (code "118") (name "/LED2") (class "Default")
      (node (ref "IC33") (pin "5") (pinfunction "Y3_5") (pintype "tri_state"))
    )
    (net (code "119") (name "/LED3") (class "Default")
      (node (ref "IC33") (pin "3") (pinfunction "Y4_3") (pintype "tri_state"))
    )
    (net (code "120") (name "/LED4") (class "Default")
      (node (ref "IC33") (pin "18") (pinfunction "Y1_18") (pintype "tri_state"))
    )
    (net (code "121") (name "/LED5") (class "Default")
      (node (ref "IC33") (pin "16") (pinfunction "Y2_16") (pintype "tri_state"))
    )
    (net (code "122") (name "/LED6") (class "Default")
      (node (ref "IC33") (pin "14") (pinfunction "Y3_14") (pintype "tri_state"))
    )
    (net (code "123") (name "/LED7") (class "Default")
      (node (ref "IC33") (pin "12") (pinfunction "Y4_12") (pintype "tri_state"))
    )
    (net (code "125") (name "GND") (class "Default")
      (node (ref "C119") (pin "1") (pinfunction "1_1") (pintype "passive"))
      (node (ref "C120") (pin "1") (pinfunction "1_1") (pintype "passive"))
      (node (ref "C124") (pin "1") (pinfunction "1_1") (pintype "passive"))
      (node (ref "C125") (pin "2") (pinfunction "2_2") (pintype "passive"))
      (node (ref "C132") (pin "1") (pinfunction "1_1") (pintype "passive"))
      (node (ref "C41") (pin "1") (pinfunction "1_1") (pintype "passive"))
      (node (ref "IC31") (pin "8") (pinfunction "GND_8") (pintype "power_in"))
      (node (ref "IC33") (pin "1") (pinfunction "~{OE}_1") (pintype "input"))
      (node (ref "IC33") (pin "10") (pinfunction "GND_10") (pintype "power_in"))
      (node (ref "IC33") (pin "19") (pinfunction "~{OE}_19") (pintype "input"))
      (node (ref "IC34") (pin "10") (pinfunction "GND_10") (pintype "power_in"))
      (node (ref "IC35") (pin "7") (pinfunction "VEE_7") (pintype "power_in"))
      (node (ref "IC35") (pin "8") (pinfunction "GND_8") (pintype "power_in"))
      (node (ref "J1") (pin "A1") (pinfunction "A1_A1") (pintype "bidirectional"))
      (node (ref "J1") (pin "A12") (pinfunction "A12_A12") (pintype "bidirectional"))
      (node (ref "J1") (pin "A15") (pinfunction "A15_A15") (pintype "bidirectional"))
      (node (ref "J1") (pin "A18") (pinfunction "A18_A18") (pintype "bidirectional"))
      (node (ref "J1") (pin "A4") (pinfunction "A4_A4") (pintype "bidirectional"))
      (node (ref "J1") (pin "A7") (pinfunction "A7_A7") (pintype "bidirectional"))
      (node (ref "J1") (pin "B1") (pinfunction "B1_B1") (pintype "bidirectional"))
      (node (ref "J1") (pin "B12") (pinfunction "B12_B12") (pintype "bidirectional"))
      (node (ref "J1") (pin "B15") (pinfunction "B15_B15") (pintype "bidirectional"))
      (node (ref "J1") (pin "B18") (pinfunction "B18_B18") (pintype "bidirectional"))
      (node (ref "J1") (pin "B4") (pinfunction "B4_B4") (pintype "bidirectional"))
      (node (ref "J1") (pin "B7") (pinfunction "B7_B7") (pintype "bidirectional"))
      (node (ref "J1") (pin "Shell1") (pinfunction "Shell1_Shell1") (pintype "bidirectional"))
      (node (ref "J1") (pin "Shell2") (pinfunction "Shell2_Shell2") (pintype "bidirectional"))
      (node (ref "J1") (pin "Shell3") (pinfunction "Shell3_Shell3") (pintype "bidirectional"))
      (node (ref "J1") (pin "Shell4") (pinfunction "Shell4_Shell4") (pintype "bidirectional"))
      (node (ref "J1") (pin "Shell5") (pinfunction "Shell5_Shell5") (pintype "bidirectional"))
      (node (ref "J13") (pin "A1") (pinfunction "A1_A1") (pintype "bidirectional"))
      (node (ref "J13") (pin "A12") (pinfunction "A12_A12") (pintype "bidirectional"))
      (node (ref "J13") (pin "A15") (pinfunction "A15_A15") (pintype "bidirectional"))
      (node (ref "J13") (pin "A18") (pinfunction "A18_A18") (pintype "bidirectional"))
      (node (ref "J13") (pin "A4") (pinfunction "A4_A4") (pintype "bidirectional"))
      (node (ref "J13") (pin "A7") (pinfunction "A7_A7") (pintype "bidirectional"))
      (node (ref "J13") (pin "B1") (pinfunction "B1_B1") (pintype "bidirectional"))
      (node (ref "J13") (pin "B12") (pinfunction "B12_B12") (pintype "bidirectional"))
      (node (ref "J13") (pin "B15") (pinfunction "B15_B15") (pintype "bidirectional"))
      (node (ref "J13") (pin "B18") (pinfunction "B18_B18") (pintype "bidirectional"))
      (node (ref "J13") (pin "B4") (pinfunction "B4_B4") (pintype "bidirectional"))
      (node (ref "J13") (pin "B7") (pinfunction "B7_B7") (pintype "bidirectional"))
      (node (ref "J13") (pin "Shell1") (pinfunction "Shell1_Shell1") (pintype "bidirectional"))
      (node (ref "J13") (pin "Shell2") (pinfunction "Shell2_Shell2") (pintype "bidirectional"))
      (node (ref "J13") (pin "Shell3") (pinfunction "Shell3_Shell3") (pintype "bidirectional"))
      (node (ref "J13") (pin "Shell4") (pinfunction "Shell4_Shell4") (pintype "bidirectional"))
      (node (ref "J13") (pin "Shell5") (pinfunction "Shell5_Shell5") (pintype "bidirectional"))
      (node (ref "J14") (pin "A1") (pinfunction "A1_A1") (pintype "bidirectional"))
      (node (ref "J14") (pin "A12") (pinfunction "A12_A12") (pintype "bidirectional"))
      (node (ref "J14") (pin "A15") (pinfunction "A15_A15") (pintype "bidirectional"))
      (node (ref "J14") (pin "A18") (pinfunction "A18_A18") (pintype "bidirectional"))
      (node (ref "J14") (pin "A4") (pinfunction "A4_A4") (pintype "bidirectional"))
      (node (ref "J14") (pin "A7") (pinfunction "A7_A7") (pintype "bidirectional"))
      (node (ref "J14") (pin "B1") (pinfunction "B1_B1") (pintype "bidirectional"))
      (node (ref "J14") (pin "B12") (pinfunction "B12_B12") (pintype "bidirectional"))
      (node (ref "J14") (pin "B15") (pinfunction "B15_B15") (pintype "bidirectional"))
      (node (ref "J14") (pin "B18") (pinfunction "B18_B18") (pintype "bidirectional"))
      (node (ref "J14") (pin "B4") (pinfunction "B4_B4") (pintype "bidirectional"))
      (node (ref "J14") (pin "B7") (pinfunction "B7_B7") (pintype "bidirectional"))
      (node (ref "J14") (pin "Shell1") (pinfunction "Shell1_Shell1") (pintype "bidirectional"))
      (node (ref "J14") (pin "Shell2") (pinfunction "Shell2_Shell2") (pintype "bidirectional"))
      (node (ref "J14") (pin "Shell4") (pinfunction "Shell4_Shell4") (pintype "bidirectional"))
      (node (ref "J14") (pin "Shell5") (pinfunction "Shell5_Shell5") (pintype "bidirectional"))
      (node (ref "J15") (pin "A1") (pinfunction "A1_A1") (pintype "bidirectional"))
      (node (ref "J15") (pin "A12") (pinfunction "A12_A12") (pintype "bidirectional"))
      (node (ref "J15") (pin "A15") (pinfunction "A15_A15") (pintype "bidirectional"))
      (node (ref "J15") (pin "A18") (pinfunction "A18_A18") (pintype "bidirectional"))
      (node (ref "J15") (pin "A4") (pinfunction "A4_A4") (pintype "bidirectional"))
      (node (ref "J15") (pin "A7") (pinfunction "A7_A7") (pintype "bidirectional"))
      (node (ref "J15") (pin "B1") (pinfunction "B1_B1") (pintype "bidirectional"))
      (node (ref "J15") (pin "B12") (pinfunction "B12_B12") (pintype "bidirectional"))
      (node (ref "J15") (pin "B15") (pinfunction "B15_B15") (pintype "bidirectional"))
      (node (ref "J15") (pin "B18") (pinfunction "B18_B18") (pintype "bidirectional"))
      (node (ref "J15") (pin "B4") (pinfunction "B4_B4") (pintype "bidirectional"))
      (node (ref "J15") (pin "B7") (pinfunction "B7_B7") (pintype "bidirectional"))
      (node (ref "J15") (pin "Shell1") (pinfunction "Shell1_Shell1") (pintype "bidirectional"))
      (node (ref "J15") (pin "Shell2") (pinfunction "Shell2_Shell2") (pintype "bidirectional"))
      (node (ref "J15") (pin "Shell3") (pinfunction "Shell3_Shell3") (pintype "bidirectional"))
      (node (ref "J15") (pin "Shell4") (pinfunction "Shell4_Shell4") (pintype "bidirectional"))
      (node (ref "J15") (pin "Shell5") (pinfunction "Shell5_Shell5") (pintype "bidirectional"))
      (node (ref "J3") (pin "12") (pinfunction "12_12") (pintype "bidirectional"))
      (node (ref "J3") (pin "15") (pinfunction "15_15") (pintype "bidirectional"))
      (node (ref "J3") (pin "18") (pinfunction "18_18") (pintype "bidirectional"))
      (node (ref "J3") (pin "21") (pinfunction "21_21") (pintype "bidirectional"))
      (node (ref "J3") (pin "24") (pinfunction "24_24") (pintype "bidirectional"))
      (node (ref "J3") (pin "3") (pinfunction "3_3") (pintype "bidirectional"))
      (node (ref "J3") (pin "6") (pinfunction "6_6") (pintype "bidirectional"))
      (node (ref "J3") (pin "9") (pinfunction "9_9") (pintype "bidirectional"))
      (node (ref "J4") (pin "12") (pinfunction "12_12") (pintype "bidirectional"))
      (node (ref "J4") (pin "15") (pinfunction "15_15") (pintype "bidirectional"))
      (node (ref "J4") (pin "18") (pinfunction "18_18") (pintype "bidirectional"))
      (node (ref "J4") (pin "21") (pinfunction "21_21") (pintype "bidirectional"))
      (node (ref "J4") (pin "24") (pinfunction "24_24") (pintype "bidirectional"))
      (node (ref "J4") (pin "3") (pinfunction "3_3") (pintype "bidirectional"))
      (node (ref "J4") (pin "6") (pinfunction "6_6") (pintype "bidirectional"))
      (node (ref "J4") (pin "9") (pinfunction "9_9") (pintype "bidirectional"))
      (node (ref "J5") (pin "12") (pinfunction "12_12") (pintype "bidirectional"))
      (node (ref "J5") (pin "15") (pinfunction "15_15") (pintype "bidirectional"))
      (node (ref "J5") (pin "18") (pinfunction "18_18") (pintype "bidirectional"))
      (node (ref "J5") (pin "21") (pinfunction "21_21") (pintype "bidirectional"))
      (node (ref "J5") (pin "24") (pinfunction "24_24") (pintype "bidirectional"))
      (node (ref "J5") (pin "3") (pinfunction "3_3") (pintype "bidirectional"))
      (node (ref "J5") (pin "6") (pinfunction "6_6") (pintype "bidirectional"))
      (node (ref "J5") (pin "9") (pinfunction "9_9") (pintype "bidirectional"))
      (node (ref "J7") (pin "12") (pinfunction "12_12") (pintype "bidirectional"))
      (node (ref "J7") (pin "15") (pinfunction "15_15") (pintype "bidirectional"))
      (node (ref "J7") (pin "18") (pinfunction "18_18") (pintype "bidirectional"))
      (node (ref "J7") (pin "21") (pinfunction "21_21") (pintype "bidirectional"))
      (node (ref "J7") (pin "24") (pinfunction "24_24") (pintype "bidirectional"))
      (node (ref "J7") (pin "3") (pinfunction "3_3") (pintype "bidirectional"))
      (node (ref "J7") (pin "6") (pinfunction "6_6") (pintype "bidirectional"))
      (node (ref "J7") (pin "9") (pinfunction "9_9") (pintype "bidirectional"))
    )
    (net (code "126") (name "N13V0_SCSI") (class "Default")
      (node (ref "J3") (pin "26") (pinfunction "26_26") (pintype "bidirectional"))
      (node (ref "J4") (pin "26") (pinfunction "26_26") (pintype "bidirectional"))
      (node (ref "J5") (pin "26") (pinfunction "26_26") (pintype "bidirectional"))
      (node (ref "J7") (pin "26") (pinfunction "26_26") (pintype "bidirectional"))
    )
    (net (code "127") (name "Net-(IC31-~{Y}0)") (class "Default")
      (node (ref "IC31") (pin "15") (pinfunction "~{Y}0_15") (pintype "output"))
      (node (ref "R281") (pin "1") (pinfunction "1_1") (pintype "passive"))
    )
    (net (code "128") (name "Net-(IC31-~{Y}1)") (class "Default")
      (node (ref "IC31") (pin "14") (pinfunction "~{Y}1_14") (pintype "output"))
      (node (ref "R282") (pin "1") (pinfunction "1_1") (pintype "passive"))
    )
    (net (code "129") (name "Net-(IC31-~{Y}2)") (class "Default")
      (node (ref "IC31") (pin "13") (pinfunction "~{Y}2_13") (pintype "output"))
      (node (ref "R283") (pin "1") (pinfunction "1_1") (pintype "passive"))
    )
    (net (code "130") (name "Net-(IC31-~{Y}3)") (class "Default")
      (node (ref "IC31") (pin "12") (pinfunction "~{Y}3_12") (pintype "output"))
      (node (ref "R284") (pin "1") (pinfunction "1_1") (pintype "passive"))
    )
    (net (code "131") (name "Net-(IC31-~{Y}4)") (class "Default")
      (node (ref "IC31") (pin "11") (pinfunction "~{Y}4_11") (pintype "output"))
      (node (ref "R285") (pin "1") (pinfunction "1_1") (pintype "passive"))
    )
    (net (code "132") (name "Net-(IC31-~{Y}5)") (class "Default")
      (node (ref "IC31") (pin "10") (pinfunction "~{Y}5_10") (pintype "output"))
      (node (ref "R286") (pin "1") (pinfunction "1_1") (pintype "passive"))
    )
    (net (code "133") (name "Net-(IC31-~{Y}6)") (class "Default")
      (node (ref "IC31") (pin "9") (pinfunction "~{Y}6_9") (pintype "output"))
      (node (ref "R287") (pin "1") (pinfunction "1_1") (pintype "passive"))
    )
    (net (code "134") (name "Net-(IC31-~{Y}7)") (class "Default")
      (node (ref "IC31") (pin "7") (pinfunction "~{Y}7_7") (pintype "output"))
      (node (ref "R288") (pin "1") (pinfunction "1_1") (pintype "passive"))
    )
    (net (code "135") (name "Net-(IC34A-Y1)") (class "Default")
      (node (ref "IC34") (pin "18") (pinfunction "Y1_18") (pintype "tri_state"))
      (node (ref "R289") (pin "1") (pinfunction "1_1") (pintype "passive"))
    )
    (net (code "136") (name "Net-(IC34A-Y2)") (class "Default")
      (node (ref "IC34") (pin "16") (pinfunction "Y2_16") (pintype "tri_state"))
      (node (ref "R290") (pin "1") (pinfunction "1_1") (pintype "passive"))
    )
    (net (code "137") (name "Net-(IC34A-Y3)") (class "Default")
      (node (ref "IC34") (pin "14") (pinfunction "Y3_14") (pintype "tri_state"))
      (node (ref "R291") (pin "1") (pinfunction "1_1") (pintype "passive"))
    )
    (net (code "138") (name "Net-(IC34A-Y4)") (class "Default")
      (node (ref "IC34") (pin "12") (pinfunction "Y4_12") (pintype "tri_state"))
      (node (ref "R292") (pin "1") (pinfunction "1_1") (pintype "passive"))
    )
    (net (code "139") (name "Net-(IC34B-Y1)") (class "Default")
      (node (ref "IC34") (pin "9") (pinfunction "Y1_9") (pintype "tri_state"))
      (node (ref "R293") (pin "1") (pinfunction "1_1") (pintype "passive"))
    )
    (net (code "140") (name "Net-(IC34B-Y2)") (class "Default")
      (node (ref "IC34") (pin "7") (pinfunction "Y2_7") (pintype "tri_state"))
      (node (ref "R294") (pin "1") (pinfunction "1_1") (pintype "passive"))
    )
    (net (code "141") (name "Net-(IC34B-Y3)") (class "Default")
      (node (ref "IC34") (pin "5") (pinfunction "Y3_5") (pintype "tri_state"))
      (node (ref "R295") (pin "1") (pinfunction "1_1") (pintype "passive"))
    )
    (net (code "142") (name "Net-(IC34B-Y4)") (class "Default")
      (node (ref "IC34") (pin "3") (pinfunction "Y4_3") (pintype "tri_state"))
      (node (ref "R296") (pin "1") (pinfunction "1_1") (pintype "passive"))
    )
    (net (code "143") (name "Net-(IC35-X)") (class "Default")
      (node (ref "IC35") (pin "3") (pinfunction "X_3") (pintype "bidirectional"))
      (node (ref "R280") (pin "1") (pinfunction "1_1") (pintype "passive"))
    )
    (net (code "144") (name "P2V5") (class "Default")
      (node (ref "R277") (pin "2") (pinfunction "2_2") (pintype "passive"))
    )
    (net (code "145") (name "P3V3") (class "Default")
      (node (ref "L6") (pin "1") (pinfunction "1_1") (pintype "passive"))
    )
    (net (code "146") (name "P3V3A") (class "Default")
      (node (ref "C119") (pin "2") (pinfunction "2_2") (pintype "passive"))
      (node (ref "C120") (pin "2") (pinfunction "2_2") (pintype "passive"))
      (node (ref "C124") (pin "2") (pinfunction "2_2") (pintype "passive"))
      (node (ref "C125") (pin "1") (pinfunction "1_1") (pintype "passive"))
      (node (ref "C132") (pin "2") (pinfunction "2_2") (pintype "passive"))
      (node (ref "C41") (pin "2") (pinfunction "2_2") (pintype "passive"))
      (node (ref "IC31") (pin "16") (pinfunction "VCC_16") (pintype "power_in"))
      (node (ref "IC31") (pin "6") (pinfunction "E3_6") (pintype "input"))
      (node (ref "IC33") (pin "20") (pinfunction "VCC_20") (pintype "power_in"))
      (node (ref "IC34") (pin "20") (pinfunction "VCC_20") (pintype "power_in"))
      (node (ref "IC35") (pin "16") (pinfunction "VCC_16") (pintype "power_in"))
      (node (ref "L6") (pin "2") (pinfunction "2_2") (pintype "passive"))
    )
    (net (code "147") (name "P13V0_SCSI") (class "Default")
      (node (ref "J3") (pin "25") (pinfunction "25_25") (pintype "bidirectional"))
      (node (ref "J4") (pin "25") (pinfunction "25_25") (pintype "bidirectional"))
      (node (ref "J5") (pin "25") (pinfunction "25_25") (pintype "bidirectional"))
      (node (ref "J7") (pin "25") (pinfunction "25_25") (pintype "bidirectional"))
    )
    (net (code "148") (name "unconnected-(J1-PadShell6)") (class "Default")
      (node (ref "J1") (pin "Shell6") (pinfunction "Shell6_Shell6") (pintype "bidirectional+no_connect"))
    )
    (net (code "149") (name "unconnected-(J13-PadShell6)") (class "Default")
      (node (ref "J13") (pin "Shell6") (pinfunction "Shell6_Shell6") (pintype "bidirectional+no_connect"))
    )
    (net (code "150") (name "unconnected-(J14-PadShell3)") (class "Default")
      (node (ref "J14") (pin "Shell3") (pinfunction "Shell3_Shell3") (pintype "bidirectional+no_connect"))
    )
    (net (code "151") (name "unconnected-(J14-PadShell6)") (class "Default")
      (node (ref "J14") (pin "Shell6") (pinfunction "Shell6_Shell6") (pintype "bidirectional+no_connect"))
    )
    (net (code "152") (name "unconnected-(J15-PadShell6)") (class "Default")
      (node (ref "J15") (pin "Shell6") (pinfunction "Shell6_Shell6") (pintype "bidirectional+no_connect"))
    )
  )
)
